# pcb01_power.net
KiCad netlist of a schematic drawn in EAGLE
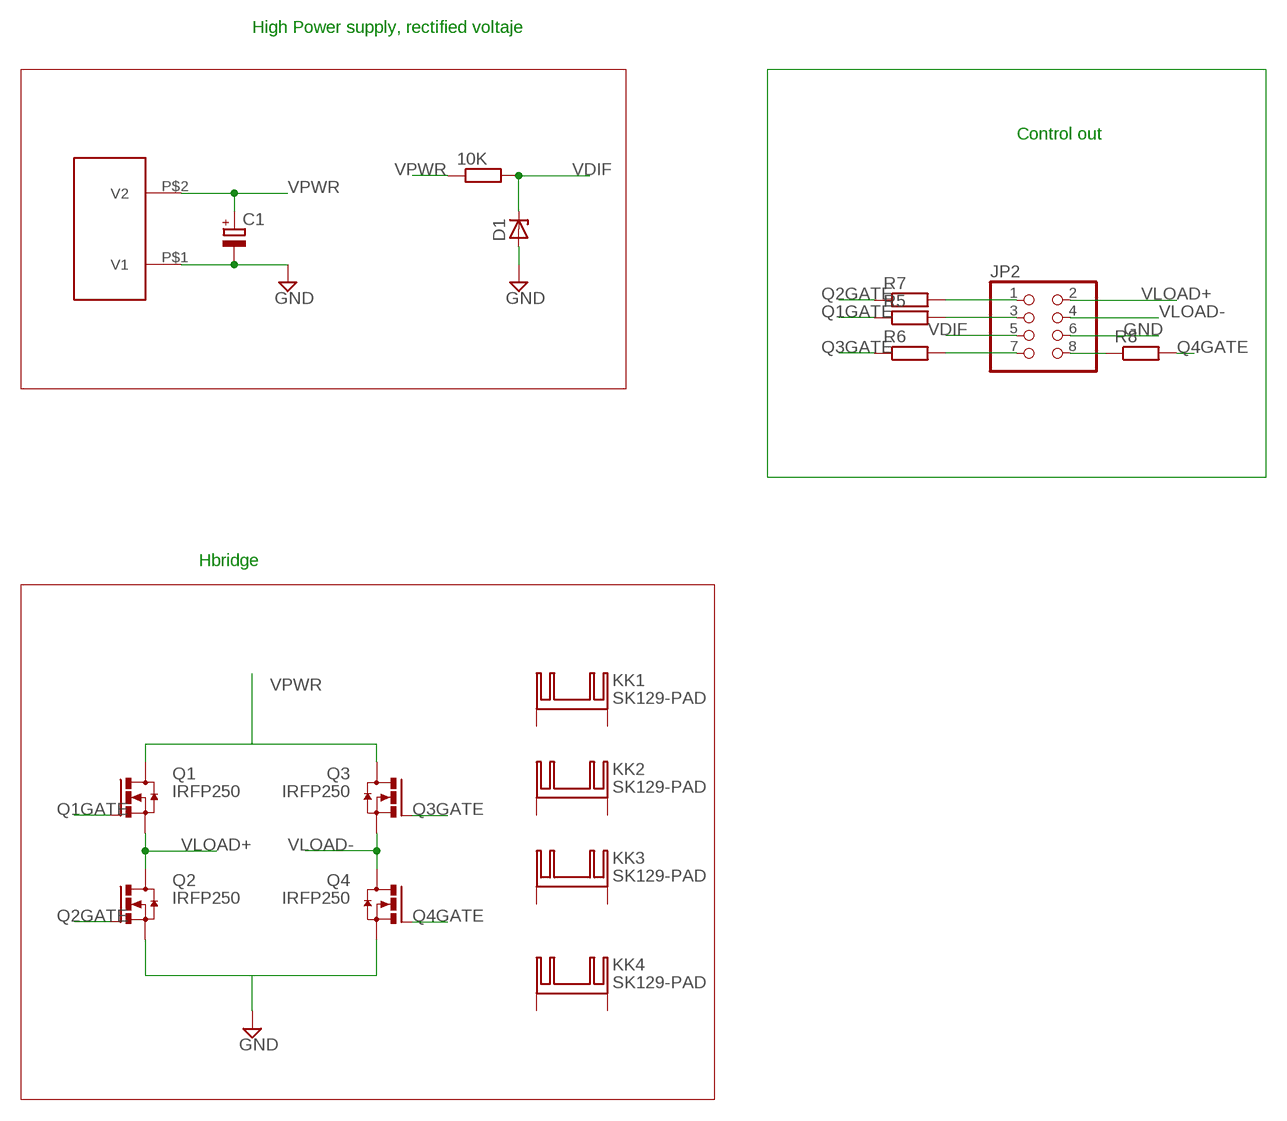
[diagram p0: schematic, sheet 1]

(export (version "E")
  (design (tool "Eeschema 10.0.6"))
  (components
    (comp (ref "10K")
      (value "R-EU_V234/12")
      (footprint "eagle-import:V234_12")
      (libsource (lib "eagle-import") (part "R-EU_V234/12"))
    )
    (comp (ref "C1")
      (value "CPOL-EUE7.5-16")
      (footprint "eagle-import:E7,5-16")
      (libsource (lib "eagle-import") (part "CPOL-EUE7.5-16"))
    )
    (comp (ref "D1")
      (value "ZENER-DIODEDO35Z10")
      (footprint "eagle-import:DO35Z10")
      (libsource (lib "eagle-import") (part "ZENER-DIODEDO35Z10"))
    )
    (comp (ref "JP2")
      (value "PINHD-2X4")
      (footprint "eagle-import:2X04")
      (libsource (lib "eagle-import") (part "PINHD-2X4"))
    )
    (comp (ref "KK1")
      (value "SK129-PAD")
      (footprint "eagle-import:SK129")
      (libsource (lib "eagle-import") (part "SK129-PAD"))
    )
    (comp (ref "KK2")
      (value "SK129-PAD")
      (footprint "eagle-import:SK129")
      (libsource (lib "eagle-import") (part "SK129-PAD"))
    )
    (comp (ref "KK3")
      (value "SK129-PAD")
      (footprint "eagle-import:SK129")
      (libsource (lib "eagle-import") (part "SK129-PAD"))
    )
    (comp (ref "KK4")
      (value "SK129-PAD")
      (footprint "eagle-import:SK129")
      (libsource (lib "eagle-import") (part "SK129-PAD"))
    )
    (comp (ref "Q1")
      (value "IRFP250")
      (footprint "eagle-import:TO-247AD-V")
      (libsource (lib "eagle-import") (part "IRFP250"))
    )
    (comp (ref "Q2")
      (value "IRFP250")
      (footprint "eagle-import:TO-247AD-V")
      (libsource (lib "eagle-import") (part "IRFP250"))
    )
    (comp (ref "Q3")
      (value "IRFP250")
      (footprint "eagle-import:TO-247AD-V")
      (libsource (lib "eagle-import") (part "IRFP250"))
    )
    (comp (ref "Q4")
      (value "IRFP250")
      (footprint "eagle-import:TO-247AD-V")
      (libsource (lib "eagle-import") (part "IRFP250"))
    )
    (comp (ref "R5")
      (value "R-EU_0207/12")
      (footprint "eagle-import:0207_12")
      (libsource (lib "eagle-import") (part "R-EU_0207/12"))
    )
    (comp (ref "R6")
      (value "R-EU_0207/12")
      (footprint "eagle-import:0207_12")
      (libsource (lib "eagle-import") (part "R-EU_0207/12"))
    )
    (comp (ref "R7")
      (value "R-EU_0207/12")
      (footprint "eagle-import:0207_12")
      (libsource (lib "eagle-import") (part "R-EU_0207/12"))
    )
    (comp (ref "R8")
      (value "R-EU_0207/12")
      (footprint "eagle-import:0207_12")
      (libsource (lib "eagle-import") (part "R-EU_0207/12"))
    )
    (comp (ref "U$1")
      (value "BIGPLUG")
      (footprint "eagle-import:BIGPLUG")
      (libsource (lib "eagle-import") (part "BIGPLUG"))
    )
  )
  (nets
    (net (code "1") (name "/Q1GATE") (class "Default")
      (node (ref "Q1") (pin "G") (pinfunction "G_G") (pintype "passive"))
      (node (ref "R5") (pin "1") (pinfunction "1_1") (pintype "passive"))
    )
    (net (code "2") (name "/Q2GATE") (class "Default")
      (node (ref "Q2") (pin "G") (pinfunction "G_G") (pintype "passive"))
      (node (ref "R7") (pin "1") (pinfunction "1_1") (pintype "passive"))
    )
    (net (code "3") (name "/Q3GATE") (class "Default")
      (node (ref "Q3") (pin "G") (pinfunction "G_G") (pintype "passive"))
      (node (ref "R6") (pin "1") (pinfunction "1_1") (pintype "passive"))
    )
    (net (code "4") (name "/Q4GATE") (class "Default")
      (node (ref "Q4") (pin "G") (pinfunction "G_G") (pintype "passive"))
      (node (ref "R8") (pin "2") (pinfunction "2_2") (pintype "passive"))
    )
    (net (code "5") (name "/VDIF") (class "Default")
      (node (ref "10K") (pin "2") (pinfunction "2_2") (pintype "passive"))
      (node (ref "D1") (pin "C") (pinfunction "C_C") (pintype "passive"))
      (node (ref "JP2") (pin "5") (pinfunction "5_5") (pintype "passive"))
    )
    (net (code "6") (name "/VLOAD+") (class "Default")
      (node (ref "JP2") (pin "2") (pinfunction "2_2") (pintype "passive"))
      (node (ref "Q1") (pin "S") (pinfunction "S_S") (pintype "passive"))
      (node (ref "Q2") (pin "D") (pinfunction "D_D") (pintype "passive"))
    )
    (net (code "7") (name "/VLOAD-") (class "Default")
      (node (ref "JP2") (pin "4") (pinfunction "4_4") (pintype "passive"))
      (node (ref "Q3") (pin "S") (pinfunction "S_S") (pintype "passive"))
      (node (ref "Q4") (pin "D") (pinfunction "D_D") (pintype "passive"))
    )
    (net (code "8") (name "/VPWR") (class "Default")
      (node (ref "10K") (pin "1") (pinfunction "1_1") (pintype "passive"))
      (node (ref "C1") (pin "+") (pinfunction "+_+") (pintype "passive"))
      (node (ref "Q1") (pin "D") (pinfunction "D_D") (pintype "passive"))
      (node (ref "Q3") (pin "D") (pinfunction "D_D") (pintype "passive"))
      (node (ref "U$1") (pin "P$2") (pinfunction "V2_P$2") (pintype "power_in"))
    )
    (net (code "9") (name "GND") (class "Default")
      (node (ref "C1") (pin "-") (pinfunction "-_-") (pintype "passive"))
      (node (ref "D1") (pin "A") (pinfunction "A_A") (pintype "passive"))
      (node (ref "JP2") (pin "6") (pinfunction "6_6") (pintype "passive"))
      (node (ref "Q2") (pin "S") (pinfunction "S_S") (pintype "passive"))
      (node (ref "Q4") (pin "S") (pinfunction "S_S") (pintype "passive"))
      (node (ref "U$1") (pin "P$1") (pinfunction "V1_P$1") (pintype "power_in"))
    )
    (net (code "10") (name "Net-(JP2-Pad1)") (class "Default")
      (node (ref "JP2") (pin "1") (pinfunction "1_1") (pintype "passive"))
      (node (ref "R7") (pin "2") (pinfunction "2_2") (pintype "passive"))
    )
    (net (code "11") (name "Net-(JP2-Pad3)") (class "Default")
      (node (ref "JP2") (pin "3") (pinfunction "3_3") (pintype "passive"))
      (node (ref "R5") (pin "2") (pinfunction "2_2") (pintype "passive"))
    )
    (net (code "12") (name "Net-(JP2-Pad7)") (class "Default")
      (node (ref "JP2") (pin "7") (pinfunction "7_7") (pintype "passive"))
      (node (ref "R6") (pin "2") (pinfunction "2_2") (pintype "passive"))
    )
    (net (code "13") (name "Net-(JP2-Pad8)") (class "Default")
      (node (ref "JP2") (pin "8") (pinfunction "8_8") (pintype "passive"))
      (node (ref "R8") (pin "1") (pinfunction "1_1") (pintype "passive"))
    )
    (net (code "14") (name "unconnected-(KK1-K-PadA2,5)") (class "Default")
      (node (ref "KK1") (pin "A2,5") (pinfunction "K_A2,5") (pintype "passive"))
    )
    (net (code "15") (name "unconnected-(KK1-K-PadB2,5)") (class "Default")
      (node (ref "KK1") (pin "B2,5") (pinfunction "K_B2,5") (pintype "passive"))
    )
    (net (code "16") (name "unconnected-(KK2-K-PadA2,5)") (class "Default")
      (node (ref "KK2") (pin "A2,5") (pinfunction "K_A2,5") (pintype "passive"))
    )
    (net (code "17") (name "unconnected-(KK2-K-PadB2,5)") (class "Default")
      (node (ref "KK2") (pin "B2,5") (pinfunction "K_B2,5") (pintype "passive"))
    )
    (net (code "18") (name "unconnected-(KK3-K-PadA2,5)") (class "Default")
      (node (ref "KK3") (pin "A2,5") (pinfunction "K_A2,5") (pintype "passive"))
    )
    (net (code "19") (name "unconnected-(KK3-K-PadB2,5)") (class "Default")
      (node (ref "KK3") (pin "B2,5") (pinfunction "K_B2,5") (pintype "passive"))
    )
    (net (code "20") (name "unconnected-(KK4-K-PadA2,5)") (class "Default")
      (node (ref "KK4") (pin "A2,5") (pinfunction "K_A2,5") (pintype "passive"))
    )
    (net (code "21") (name "unconnected-(KK4-K-PadB2,5)") (class "Default")
      (node (ref "KK4") (pin "B2,5") (pinfunction "K_B2,5") (pintype "passive"))
    )
  )
)
